# LED-PCB_Master.net
KiCad netlist of a schematic drawn in Altium Designer
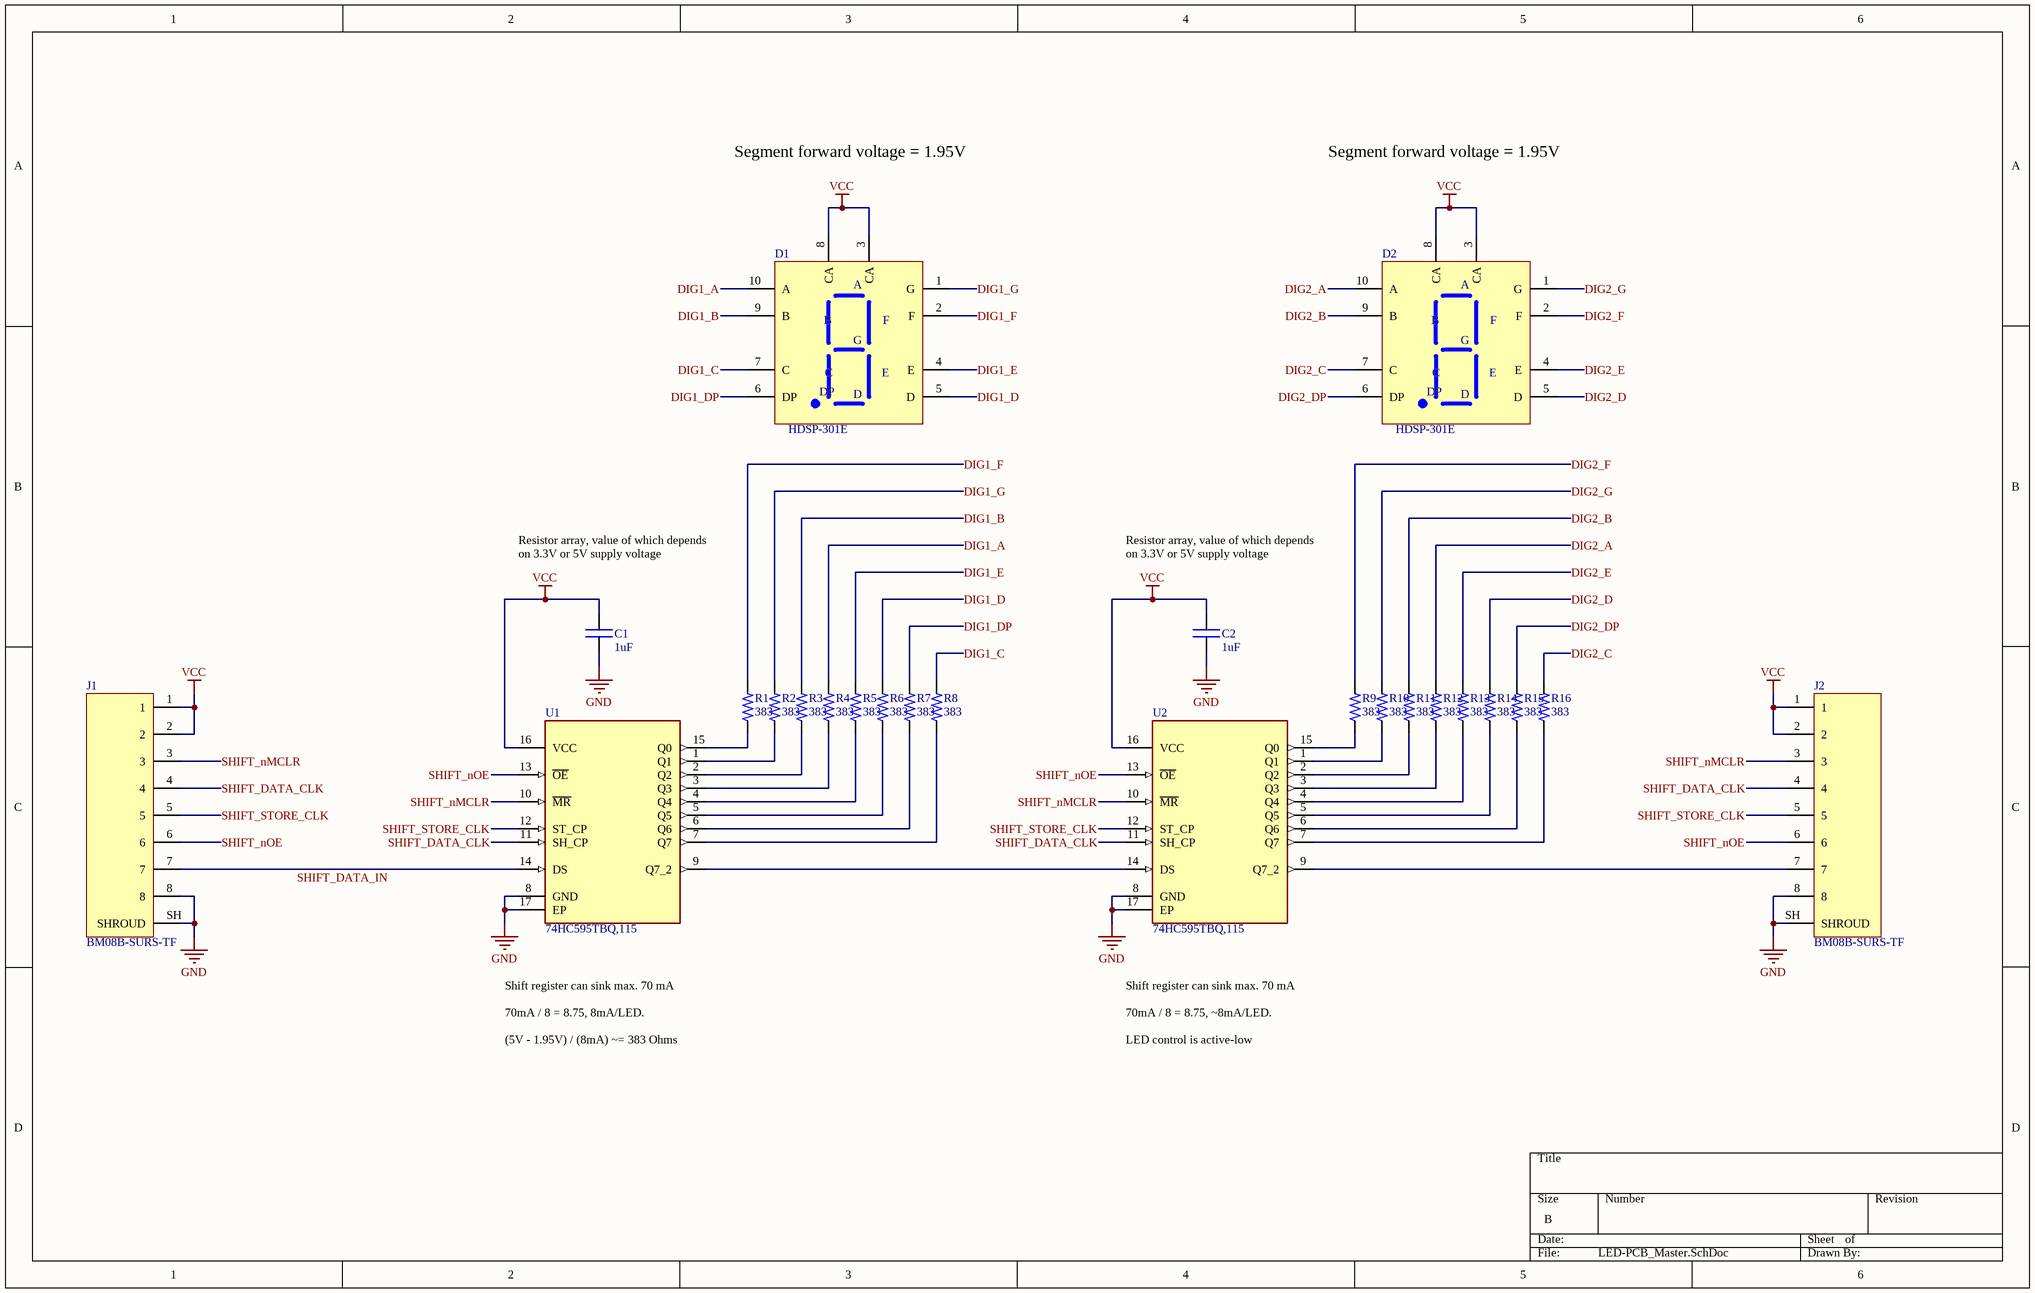
[diagram p0: LED-PCB_Master.SchDoc]

(export (version "E")
  (design (tool "Eeschema 10.0.6"))
  (components
    (comp (ref "C1")
      (value "1uF")
      (footprint "Beethoven-clock:0402C")
      (description "Capacitor")
      (fields (field (name "MFR") "Murata Electronics") (field (name "Comment") "CAP"))
      (libsource (lib "Beethoven-clock") (part "CAP"))
    )
    (comp (ref "C2")
      (value "1uF")
      (footprint "Beethoven-clock:0402C")
      (description "Capacitor")
      (fields (field (name "MFR") "Murata Electronics") (field (name "Comment") "CAP"))
      (libsource (lib "Beethoven-clock") (part "CAP"))
    )
    (comp (ref "D1")
      (value "HDSP-301E")
      (footprint "Beethoven-clock:10-DIP_7SEG")
      (description "DISPLAY 7-SEG 0.4\" SGL RED 10DIP")
      (fields (field (name "MFR") "Broadcom Limited"))
      (libsource (lib "Beethoven-clock") (part "7SEG SINGLE TH"))
    )
    (comp (ref "D2")
      (value "HDSP-301E")
      (footprint "Beethoven-clock:10-DIP_7SEG")
      (description "DISPLAY 7-SEG 0.4\" SGL RED 10DIP")
      (fields (field (name "MFR") "Broadcom Limited"))
      (libsource (lib "Beethoven-clock") (part "7SEG SINGLE TH"))
    )
    (comp (ref "J1")
      (value "BM08B-SURS-TF")
      (footprint "Beethoven-clock:JST_BM08B-SURS-TF(LF)(SN)")
      (description "CONN HEADER SMD 8POS 0.8MM")
      (fields (field (name "MFR") "JST"))
      (libsource (lib "") (part "CONN 8POS 0.8MM PITCH_1"))
    )
    (comp (ref "J2")
      (value "BM08B-SURS-TF")
      (footprint "Beethoven-clock:JST_BM08B-SURS-TF(LF)(SN)")
      (description "CONN HEADER SMD 8POS 0.8MM")
      (fields (field (name "MFR") "JST"))
      (libsource (lib "Beethoven-clock") (part "CONN 8POS 0.8MM PITCH"))
    )
    (comp (ref "R1")
      (value "383")
      (footprint "Beethoven-clock:0402R")
      (description "Resistor")
      (fields (field (name "MFR") "YAGEO") (field (name "Comment") "RES"))
      (libsource (lib "Beethoven-clock") (part "RES"))
    )
    (comp (ref "R2")
      (value "383")
      (footprint "Beethoven-clock:0402R")
      (description "Resistor")
      (fields (field (name "MFR") "YAGEO") (field (name "Comment") "RES"))
      (libsource (lib "Beethoven-clock") (part "RES"))
    )
    (comp (ref "R3")
      (value "383")
      (footprint "Beethoven-clock:0402R")
      (description "Resistor")
      (fields (field (name "MFR") "YAGEO") (field (name "Comment") "RES"))
      (libsource (lib "Beethoven-clock") (part "RES"))
    )
    (comp (ref "R4")
      (value "383")
      (footprint "Beethoven-clock:0402R")
      (description "Resistor")
      (fields (field (name "MFR") "YAGEO") (field (name "Comment") "RES"))
      (libsource (lib "Beethoven-clock") (part "RES"))
    )
    (comp (ref "R5")
      (value "383")
      (footprint "Beethoven-clock:0402R")
      (description "Resistor")
      (fields (field (name "MFR") "YAGEO") (field (name "Comment") "RES"))
      (libsource (lib "Beethoven-clock") (part "RES"))
    )
    (comp (ref "R6")
      (value "383")
      (footprint "Beethoven-clock:0402R")
      (description "Resistor")
      (fields (field (name "MFR") "YAGEO") (field (name "Comment") "RES"))
      (libsource (lib "Beethoven-clock") (part "RES"))
    )
    (comp (ref "R7")
      (value "383")
      (footprint "Beethoven-clock:0402R")
      (description "Resistor")
      (fields (field (name "MFR") "YAGEO") (field (name "Comment") "RES"))
      (libsource (lib "Beethoven-clock") (part "RES"))
    )
    (comp (ref "R8")
      (value "383")
      (footprint "Beethoven-clock:0402R")
      (description "Resistor")
      (fields (field (name "MFR") "YAGEO") (field (name "Comment") "RES"))
      (libsource (lib "Beethoven-clock") (part "RES"))
    )
    (comp (ref "R9")
      (value "383")
      (footprint "Beethoven-clock:0402R")
      (description "Resistor")
      (fields (field (name "MFR") "YAGEO") (field (name "Comment") "RES"))
      (libsource (lib "Beethoven-clock") (part "RES"))
    )
    (comp (ref "R10")
      (value "383")
      (footprint "Beethoven-clock:0402R")
      (description "Resistor")
      (fields (field (name "MFR") "YAGEO") (field (name "Comment") "RES"))
      (libsource (lib "Beethoven-clock") (part "RES"))
    )
    (comp (ref "R11")
      (value "383")
      (footprint "Beethoven-clock:0402R")
      (description "Resistor")
      (fields (field (name "MFR") "YAGEO") (field (name "Comment") "RES"))
      (libsource (lib "Beethoven-clock") (part "RES"))
    )
    (comp (ref "R12")
      (value "383")
      (footprint "Beethoven-clock:0402R")
      (description "Resistor")
      (fields (field (name "MFR") "YAGEO") (field (name "Comment") "RES"))
      (libsource (lib "Beethoven-clock") (part "RES"))
    )
    (comp (ref "R13")
      (value "383")
      (footprint "Beethoven-clock:0402R")
      (description "Resistor")
      (fields (field (name "MFR") "YAGEO") (field (name "Comment") "RES"))
      (libsource (lib "Beethoven-clock") (part "RES"))
    )
    (comp (ref "R14")
      (value "383")
      (footprint "Beethoven-clock:0402R")
      (description "Resistor")
      (fields (field (name "MFR") "YAGEO") (field (name "Comment") "RES"))
      (libsource (lib "Beethoven-clock") (part "RES"))
    )
    (comp (ref "R15")
      (value "383")
      (footprint "Beethoven-clock:0402R")
      (description "Resistor")
      (fields (field (name "MFR") "YAGEO") (field (name "Comment") "RES"))
      (libsource (lib "Beethoven-clock") (part "RES"))
    )
    (comp (ref "R16")
      (value "383")
      (footprint "Beethoven-clock:0402R")
      (description "Resistor")
      (fields (field (name "MFR") "YAGEO") (field (name "Comment") "RES"))
      (libsource (lib "Beethoven-clock") (part "RES"))
    )
    (comp (ref "U1")
      (value "74HC595TBQ,115")
      (footprint "Beethoven-clock:16-VFQN-EP")
      (description "IC 8BIT SHIFT REGISTER 16-DHVQFN")
      (fields (field (name "MFR") "Nexperia USA Inc."))
      (libsource (lib "Beethoven-clock") (part "SHIFT REG 8BIT QFN"))
    )
    (comp (ref "U2")
      (value "74HC595TBQ,115")
      (footprint "Beethoven-clock:16-VFQN-EP")
      (description "IC 8BIT SHIFT REGISTER 16-DHVQFN")
      (fields (field (name "MFR") "Nexperia USA Inc."))
      (libsource (lib "Beethoven-clock") (part "SHIFT REG 8BIT QFN"))
    )
  )
  (nets
    (net (code "1") (name "/DIG1_A") (class "Default")
      (node (ref "D1") (pin "10") (pinfunction "A_10") (pintype "passive"))
      (node (ref "R4") (pin "2") (pinfunction "2_2") (pintype "passive"))
    )
    (net (code "2") (name "/DIG1_B") (class "Default")
      (node (ref "D1") (pin "9") (pinfunction "B_9") (pintype "passive"))
      (node (ref "R3") (pin "2") (pinfunction "2_2") (pintype "passive"))
    )
    (net (code "3") (name "/DIG1_C") (class "Default")
      (node (ref "D1") (pin "7") (pinfunction "C_7") (pintype "passive"))
      (node (ref "R8") (pin "2") (pinfunction "2_2") (pintype "passive"))
    )
    (net (code "4") (name "/DIG1_D") (class "Default")
      (node (ref "D1") (pin "5") (pinfunction "D_5") (pintype "passive"))
      (node (ref "R6") (pin "2") (pinfunction "2_2") (pintype "passive"))
    )
    (net (code "5") (name "/DIG1_DP") (class "Default")
      (node (ref "D1") (pin "6") (pinfunction "DP_6") (pintype "passive"))
      (node (ref "R7") (pin "2") (pinfunction "2_2") (pintype "passive"))
    )
    (net (code "6") (name "/DIG1_E") (class "Default")
      (node (ref "D1") (pin "4") (pinfunction "E_4") (pintype "passive"))
      (node (ref "R5") (pin "2") (pinfunction "2_2") (pintype "passive"))
    )
    (net (code "7") (name "/DIG1_F") (class "Default")
      (node (ref "D1") (pin "2") (pinfunction "F_2") (pintype "passive"))
      (node (ref "R1") (pin "2") (pinfunction "2_2") (pintype "passive"))
    )
    (net (code "8") (name "/DIG1_G") (class "Default")
      (node (ref "D1") (pin "1") (pinfunction "G_1") (pintype "passive"))
      (node (ref "R2") (pin "2") (pinfunction "2_2") (pintype "passive"))
    )
    (net (code "9") (name "/DIG2_A") (class "Default")
      (node (ref "D2") (pin "10") (pinfunction "A_10") (pintype "passive"))
      (node (ref "R12") (pin "2") (pinfunction "2_2") (pintype "passive"))
    )
    (net (code "10") (name "/DIG2_B") (class "Default")
      (node (ref "D2") (pin "9") (pinfunction "B_9") (pintype "passive"))
      (node (ref "R11") (pin "2") (pinfunction "2_2") (pintype "passive"))
    )
    (net (code "11") (name "/DIG2_C") (class "Default")
      (node (ref "D2") (pin "7") (pinfunction "C_7") (pintype "passive"))
      (node (ref "R16") (pin "2") (pinfunction "2_2") (pintype "passive"))
    )
    (net (code "12") (name "/DIG2_D") (class "Default")
      (node (ref "D2") (pin "5") (pinfunction "D_5") (pintype "passive"))
      (node (ref "R14") (pin "2") (pinfunction "2_2") (pintype "passive"))
    )
    (net (code "13") (name "/DIG2_DP") (class "Default")
      (node (ref "D2") (pin "6") (pinfunction "DP_6") (pintype "passive"))
      (node (ref "R15") (pin "2") (pinfunction "2_2") (pintype "passive"))
    )
    (net (code "14") (name "/DIG2_E") (class "Default")
      (node (ref "D2") (pin "4") (pinfunction "E_4") (pintype "passive"))
      (node (ref "R13") (pin "2") (pinfunction "2_2") (pintype "passive"))
    )
    (net (code "15") (name "/DIG2_F") (class "Default")
      (node (ref "D2") (pin "2") (pinfunction "F_2") (pintype "passive"))
      (node (ref "R9") (pin "2") (pinfunction "2_2") (pintype "passive"))
    )
    (net (code "16") (name "/DIG2_G") (class "Default")
      (node (ref "D2") (pin "1") (pinfunction "G_1") (pintype "passive"))
      (node (ref "R10") (pin "2") (pinfunction "2_2") (pintype "passive"))
    )
    (net (code "17") (name "/SHIFT_DATA_CLK") (class "Default")
      (node (ref "J1") (pin "4") (pinfunction "4_4") (pintype "passive"))
      (node (ref "J2") (pin "4") (pinfunction "4_4") (pintype "passive"))
      (node (ref "U1") (pin "11") (pinfunction "SH_CP_11") (pintype "input"))
      (node (ref "U2") (pin "11") (pinfunction "SH_CP_11") (pintype "input"))
    )
    (net (code "18") (name "/SHIFT_DATA_IN") (class "Default")
      (node (ref "J1") (pin "7") (pinfunction "7_7") (pintype "passive"))
      (node (ref "U1") (pin "14") (pinfunction "DS_14") (pintype "input"))
    )
    (net (code "19") (name "/SHIFT_STORE_CLK") (class "Default")
      (node (ref "J1") (pin "5") (pinfunction "5_5") (pintype "passive"))
      (node (ref "J2") (pin "5") (pinfunction "5_5") (pintype "passive"))
      (node (ref "U1") (pin "12") (pinfunction "ST_CP_12") (pintype "input"))
      (node (ref "U2") (pin "12") (pinfunction "ST_CP_12") (pintype "input"))
    )
    (net (code "20") (name "/SHIFT_nMCLR") (class "Default")
      (node (ref "J1") (pin "3") (pinfunction "3_3") (pintype "passive"))
      (node (ref "J2") (pin "3") (pinfunction "3_3") (pintype "passive"))
      (node (ref "U1") (pin "10") (pinfunction "~{MR}_10") (pintype "input"))
      (node (ref "U2") (pin "10") (pinfunction "~{MR}_10") (pintype "input"))
    )
    (net (code "21") (name "/SHIFT_nOE") (class "Default")
      (node (ref "J1") (pin "6") (pinfunction "6_6") (pintype "passive"))
      (node (ref "J2") (pin "6") (pinfunction "6_6") (pintype "passive"))
      (node (ref "U1") (pin "13") (pinfunction "~{OE}_13") (pintype "input"))
      (node (ref "U2") (pin "13") (pinfunction "~{OE}_13") (pintype "input"))
    )
    (net (code "22") (name "GND") (class "Default")
      (node (ref "C1") (pin "2") (pinfunction "2_2") (pintype "passive"))
      (node (ref "C2") (pin "2") (pinfunction "2_2") (pintype "passive"))
      (node (ref "J1") (pin "8") (pinfunction "8_8") (pintype "passive"))
      (node (ref "J1") (pin "SH") (pinfunction "SHROUD_SH") (pintype "passive"))
      (node (ref "J2") (pin "8") (pinfunction "8_8") (pintype "passive"))
      (node (ref "J2") (pin "SH") (pinfunction "SHROUD_SH") (pintype "passive"))
      (node (ref "U1") (pin "17") (pinfunction "EP_17") (pintype "passive"))
      (node (ref "U1") (pin "8") (pinfunction "GND_8") (pintype "passive"))
      (node (ref "U2") (pin "17") (pinfunction "EP_17") (pintype "passive"))
      (node (ref "U2") (pin "8") (pinfunction "GND_8") (pintype "passive"))
    )
    (net (code "23") (name "Net-(U1-Q0)") (class "Default")
      (node (ref "R1") (pin "1") (pinfunction "1_1") (pintype "passive"))
      (node (ref "U1") (pin "15") (pinfunction "Q0_15") (pintype "output"))
    )
    (net (code "24") (name "Net-(U1-Q1)") (class "Default")
      (node (ref "R2") (pin "1") (pinfunction "1_1") (pintype "passive"))
      (node (ref "U1") (pin "1") (pinfunction "Q1_1") (pintype "output"))
    )
    (net (code "25") (name "Net-(U1-Q2)") (class "Default")
      (node (ref "R3") (pin "1") (pinfunction "1_1") (pintype "passive"))
      (node (ref "U1") (pin "2") (pinfunction "Q2_2") (pintype "output"))
    )
    (net (code "26") (name "Net-(U1-Q3)") (class "Default")
      (node (ref "R4") (pin "1") (pinfunction "1_1") (pintype "passive"))
      (node (ref "U1") (pin "3") (pinfunction "Q3_3") (pintype "output"))
    )
    (net (code "27") (name "Net-(U1-Q4)") (class "Default")
      (node (ref "R5") (pin "1") (pinfunction "1_1") (pintype "passive"))
      (node (ref "U1") (pin "4") (pinfunction "Q4_4") (pintype "output"))
    )
    (net (code "28") (name "Net-(U1-Q5)") (class "Default")
      (node (ref "R6") (pin "1") (pinfunction "1_1") (pintype "passive"))
      (node (ref "U1") (pin "5") (pinfunction "Q5_5") (pintype "output"))
    )
    (net (code "29") (name "Net-(U1-Q6)") (class "Default")
      (node (ref "R7") (pin "1") (pinfunction "1_1") (pintype "passive"))
      (node (ref "U1") (pin "6") (pinfunction "Q6_6") (pintype "output"))
    )
    (net (code "30") (name "Net-(U1-Q7)") (class "Default")
      (node (ref "R8") (pin "1") (pinfunction "1_1") (pintype "passive"))
      (node (ref "U1") (pin "7") (pinfunction "Q7_7") (pintype "output"))
    )
    (net (code "31") (name "Net-(U1-Q7_2)") (class "Default")
      (node (ref "U1") (pin "9") (pinfunction "Q7_2_9") (pintype "output"))
      (node (ref "U2") (pin "14") (pinfunction "DS_14") (pintype "input"))
    )
    (net (code "32") (name "Net-(U2-Q0)") (class "Default")
      (node (ref "R9") (pin "1") (pinfunction "1_1") (pintype "passive"))
      (node (ref "U2") (pin "15") (pinfunction "Q0_15") (pintype "output"))
    )
    (net (code "33") (name "Net-(U2-Q1)") (class "Default")
      (node (ref "R10") (pin "1") (pinfunction "1_1") (pintype "passive"))
      (node (ref "U2") (pin "1") (pinfunction "Q1_1") (pintype "output"))
    )
    (net (code "34") (name "Net-(U2-Q2)") (class "Default")
      (node (ref "R11") (pin "1") (pinfunction "1_1") (pintype "passive"))
      (node (ref "U2") (pin "2") (pinfunction "Q2_2") (pintype "output"))
    )
    (net (code "35") (name "Net-(U2-Q3)") (class "Default")
      (node (ref "R12") (pin "1") (pinfunction "1_1") (pintype "passive"))
      (node (ref "U2") (pin "3") (pinfunction "Q3_3") (pintype "output"))
    )
    (net (code "36") (name "Net-(U2-Q4)") (class "Default")
      (node (ref "R13") (pin "1") (pinfunction "1_1") (pintype "passive"))
      (node (ref "U2") (pin "4") (pinfunction "Q4_4") (pintype "output"))
    )
    (net (code "37") (name "Net-(U2-Q5)") (class "Default")
      (node (ref "R14") (pin "1") (pinfunction "1_1") (pintype "passive"))
      (node (ref "U2") (pin "5") (pinfunction "Q5_5") (pintype "output"))
    )
    (net (code "38") (name "Net-(U2-Q6)") (class "Default")
      (node (ref "R15") (pin "1") (pinfunction "1_1") (pintype "passive"))
      (node (ref "U2") (pin "6") (pinfunction "Q6_6") (pintype "output"))
    )
    (net (code "39") (name "Net-(U2-Q7)") (class "Default")
      (node (ref "R16") (pin "1") (pinfunction "1_1") (pintype "passive"))
      (node (ref "U2") (pin "7") (pinfunction "Q7_7") (pintype "output"))
    )
    (net (code "40") (name "Net-(U2-Q7_2)") (class "Default")
      (node (ref "J2") (pin "7") (pinfunction "7_7") (pintype "passive"))
      (node (ref "U2") (pin "9") (pinfunction "Q7_2_9") (pintype "output"))
    )
    (net (code "41") (name "VCC") (class "Default")
      (node (ref "C1") (pin "1") (pinfunction "1_1") (pintype "passive"))
      (node (ref "C2") (pin "1") (pinfunction "1_1") (pintype "passive"))
      (node (ref "D1") (pin "3") (pinfunction "CA_3") (pintype "passive"))
      (node (ref "D1") (pin "8") (pinfunction "CA_8") (pintype "passive"))
      (node (ref "D2") (pin "3") (pinfunction "CA_3") (pintype "passive"))
      (node (ref "D2") (pin "8") (pinfunction "CA_8") (pintype "passive"))
      (node (ref "J1") (pin "1") (pinfunction "1_1") (pintype "passive"))
      (node (ref "J1") (pin "2") (pinfunction "2_2") (pintype "passive"))
      (node (ref "J2") (pin "1") (pinfunction "1_1") (pintype "passive"))
      (node (ref "J2") (pin "2") (pinfunction "2_2") (pintype "passive"))
      (node (ref "U1") (pin "16") (pinfunction "VCC_16") (pintype "power_in"))
      (node (ref "U2") (pin "16") (pinfunction "VCC_16") (pintype "power_in"))
    )
  )
)
